# JPC_XE1AP_rev_A.net
KiCad netlist of a schematic drawn in EAGLE
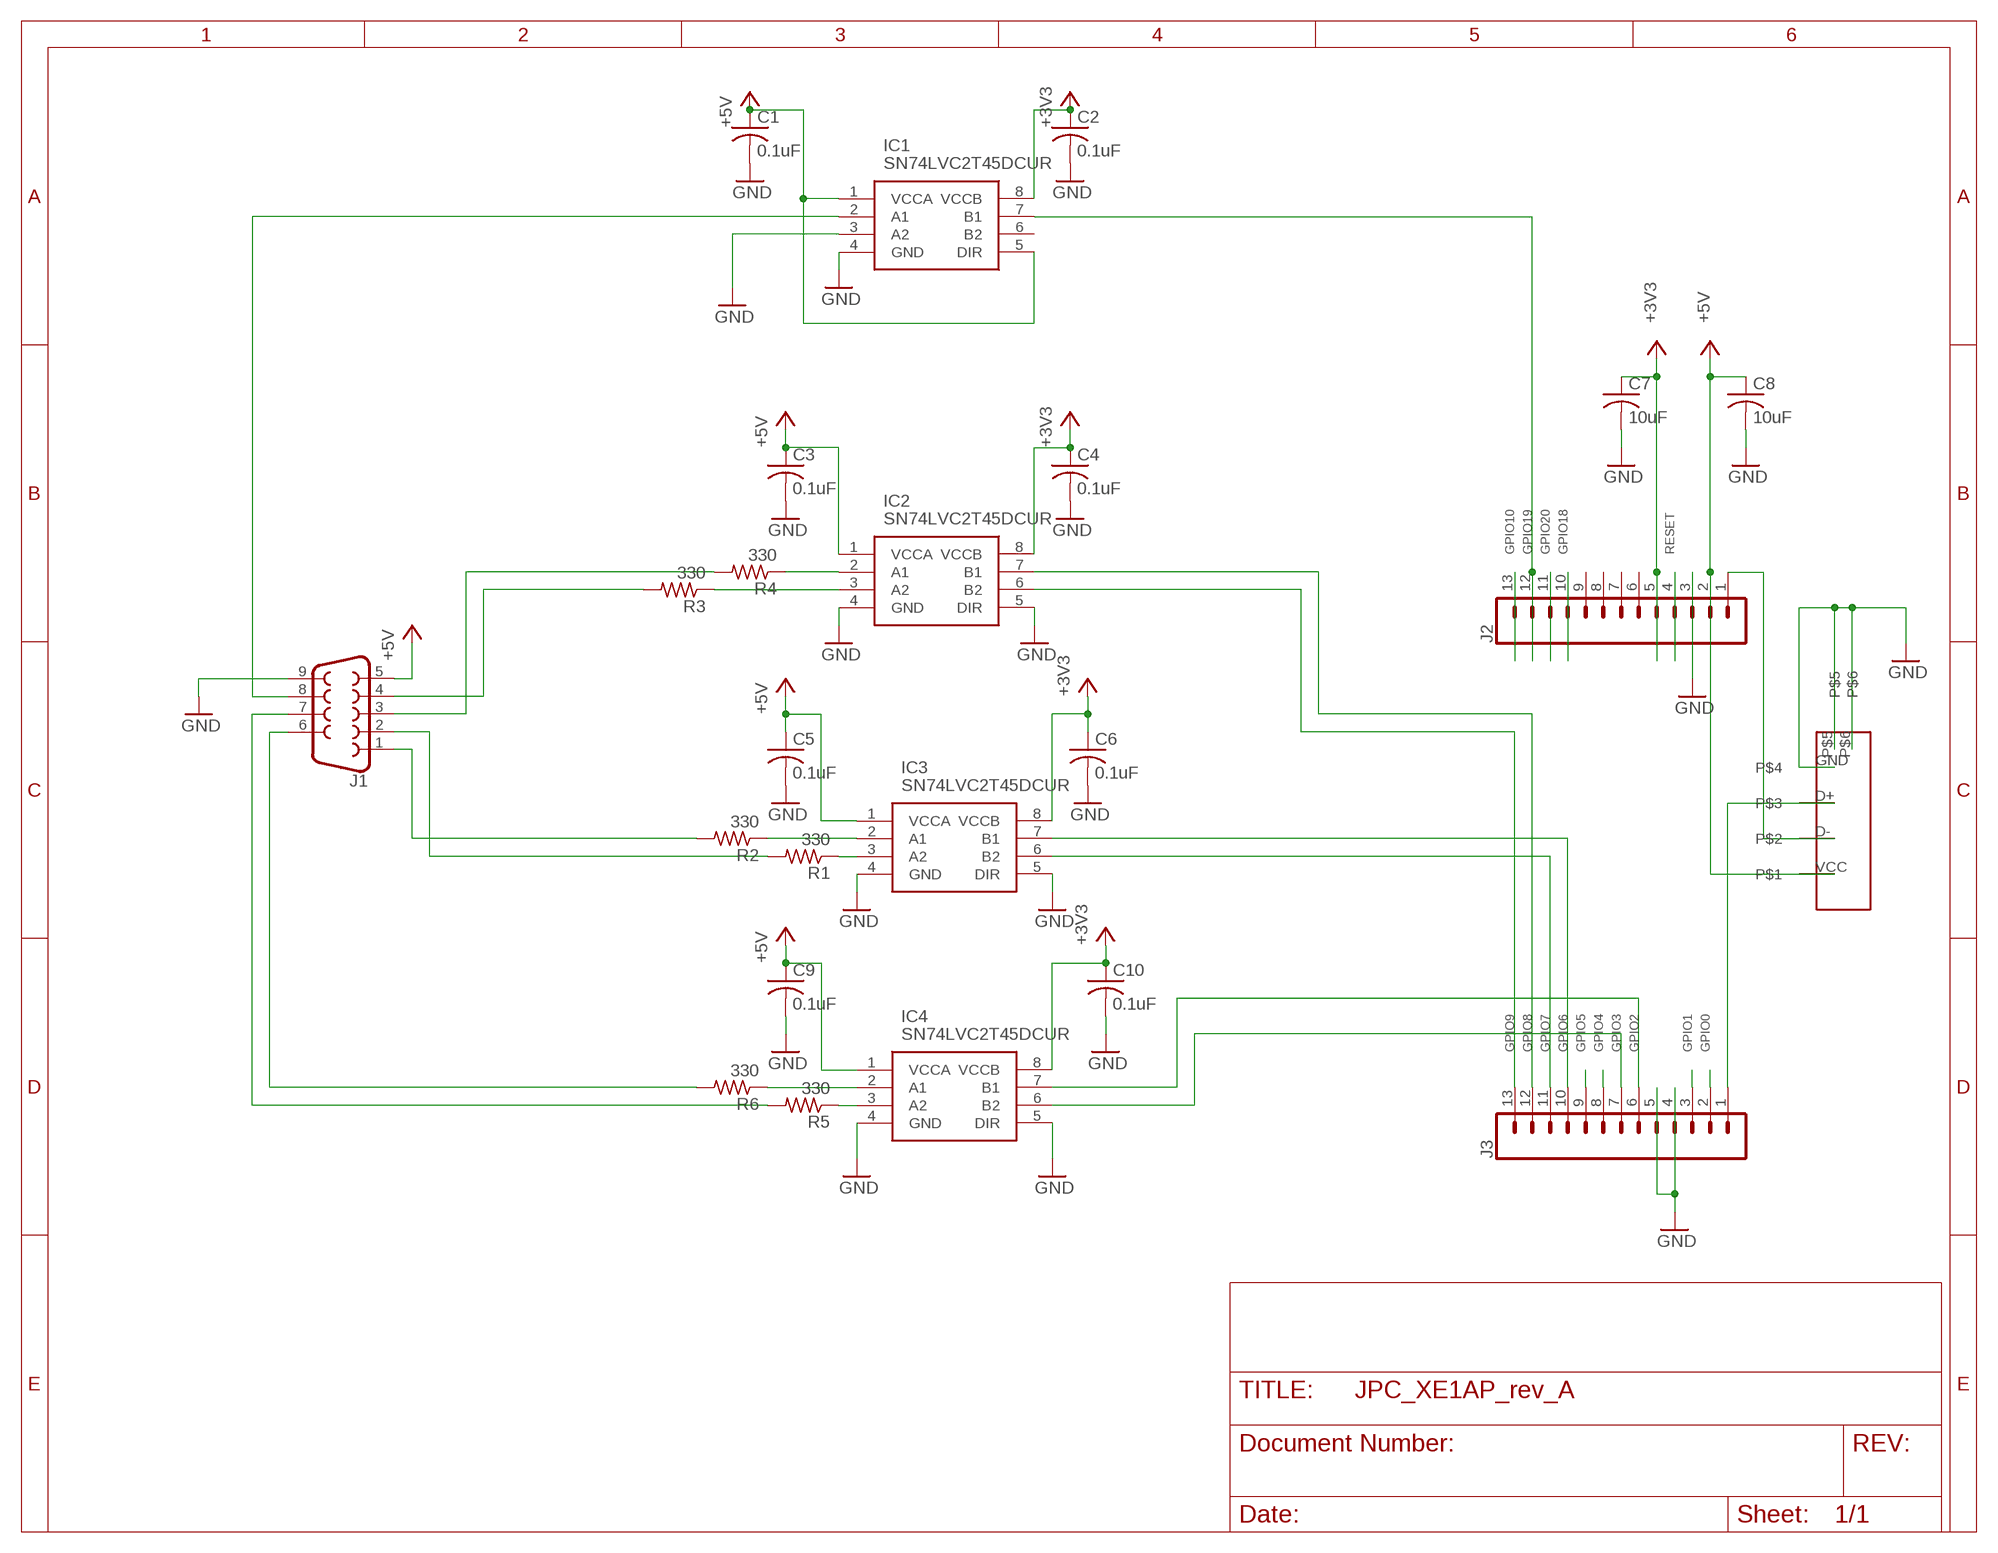
[diagram p0: schematic, sheet 1]

(export (version "E")
  (design (tool "Eeschema 10.0.6"))
  (components
    (comp (ref "C1")
      (value "0.1uF")
      (footprint "eagle-import:C0402")
      (libsource (lib "eagle-import") (part "C-USC0402"))
    )
    (comp (ref "C2")
      (value "0.1uF")
      (footprint "eagle-import:C0402")
      (libsource (lib "eagle-import") (part "C-USC0402"))
    )
    (comp (ref "C3")
      (value "0.1uF")
      (footprint "eagle-import:C0402")
      (libsource (lib "eagle-import") (part "C-USC0402"))
    )
    (comp (ref "C4")
      (value "0.1uF")
      (footprint "eagle-import:C0402")
      (libsource (lib "eagle-import") (part "C-USC0402"))
    )
    (comp (ref "C5")
      (value "0.1uF")
      (footprint "eagle-import:C0402")
      (libsource (lib "eagle-import") (part "C-USC0402"))
    )
    (comp (ref "C6")
      (value "0.1uF")
      (footprint "eagle-import:C0402")
      (libsource (lib "eagle-import") (part "C-USC0402"))
    )
    (comp (ref "C7")
      (value "10uF")
      (footprint "eagle-import:C0805")
      (libsource (lib "eagle-import") (part "resistor_348_C-USC0805"))
    )
    (comp (ref "C8")
      (value "10uF")
      (footprint "eagle-import:C0805")
      (libsource (lib "eagle-import") (part "resistor_348_C-USC0805"))
    )
    (comp (ref "C9")
      (value "0.1uF")
      (footprint "eagle-import:C0402")
      (libsource (lib "eagle-import") (part "C-USC0402"))
    )
    (comp (ref "C10")
      (value "0.1uF")
      (footprint "eagle-import:C0402")
      (libsource (lib "eagle-import") (part "C-USC0402"))
    )
    (comp (ref "IC1")
      (value "SN74LVC2T45DCUR")
      (footprint "eagle-import:SOP50P310X90-8N")
      (fields (field (name "MOUSER_PART_NUMBER") "595-SN74LVC2T45DCUR"))
      (libsource (lib "eagle-import") (part "SN74LVC2T45DCUR"))
    )
    (comp (ref "IC2")
      (value "SN74LVC2T45DCUR")
      (footprint "eagle-import:SOP50P310X90-8N")
      (fields (field (name "MOUSER_PART_NUMBER") "595-SN74LVC2T45DCUR"))
      (libsource (lib "eagle-import") (part "SN74LVC2T45DCUR"))
    )
    (comp (ref "IC3")
      (value "SN74LVC2T45DCUR")
      (footprint "eagle-import:SOP50P310X90-8N")
      (fields (field (name "MOUSER_PART_NUMBER") "595-SN74LVC2T45DCUR"))
      (libsource (lib "eagle-import") (part "SN74LVC2T45DCUR"))
    )
    (comp (ref "IC4")
      (value "SN74LVC2T45DCUR")
      (footprint "eagle-import:SOP50P310X90-8N")
      (fields (field (name "MOUSER_PART_NUMBER") "595-SN74LVC2T45DCUR"))
      (libsource (lib "eagle-import") (part "SN74LVC2T45DCUR"))
    )
    (comp (ref "J1")
      (value "DB9FEMALE")
      (footprint "eagle-import:DB9")
      (libsource (lib "eagle-import") (part "DB9FEMALE"))
    )
    (comp (ref "J2")
      (value "CONN_131X13-LONGPADS-B")
      (footprint "eagle-import:1X13-LONGPADS-B")
      (libsource (lib "eagle-import") (part "CONN_131X13-LONGPADS-B"))
    )
    (comp (ref "J3")
      (value "CONN_13LONGPADS")
      (footprint "eagle-import:1X13-LONGPADS")
      (libsource (lib "eagle-import") (part "CONN_13LONGPADS"))
    )
    (comp (ref "R1")
      (value "330")
      (footprint "eagle-import:R0402")
      (libsource (lib "eagle-import") (part "R-US_R0402"))
    )
    (comp (ref "R2")
      (value "330")
      (footprint "eagle-import:R0402")
      (libsource (lib "eagle-import") (part "R-US_R0402"))
    )
    (comp (ref "R3")
      (value "330")
      (footprint "eagle-import:R0402")
      (libsource (lib "eagle-import") (part "R-US_R0402"))
    )
    (comp (ref "R4")
      (value "330")
      (footprint "eagle-import:R0402")
      (libsource (lib "eagle-import") (part "R-US_R0402"))
    )
    (comp (ref "R5")
      (value "330")
      (footprint "eagle-import:R0402")
      (libsource (lib "eagle-import") (part "R-US_R0402"))
    )
    (comp (ref "R6")
      (value "330")
      (footprint "eagle-import:R0402")
      (libsource (lib "eagle-import") (part "R-US_R0402"))
    )
    (comp (ref "U$1")
      (value "912-121A2026S10100")
      (footprint "eagle-import:912-121A2026S10100")
      (libsource (lib "eagle-import") (part "912-121A2026S10100"))
    )
  )
  (nets
    (net (code "1") (name "+3V3") (class "Default")
      (node (ref "C10") (pin "1") (pinfunction "1_1") (pintype "passive"))
      (node (ref "C2") (pin "1") (pinfunction "1_1") (pintype "passive"))
      (node (ref "C4") (pin "1") (pinfunction "1_1") (pintype "passive"))
      (node (ref "C6") (pin "1") (pinfunction "1_1") (pintype "passive"))
      (node (ref "C7") (pin "1") (pinfunction "1_1") (pintype "passive"))
      (node (ref "IC1") (pin "8") (pinfunction "VCCB_8") (pintype "bidirectional"))
      (node (ref "IC2") (pin "8") (pinfunction "VCCB_8") (pintype "bidirectional"))
      (node (ref "IC3") (pin "8") (pinfunction "VCCB_8") (pintype "bidirectional"))
      (node (ref "IC4") (pin "8") (pinfunction "VCCB_8") (pintype "bidirectional"))
      (node (ref "J2") (pin "5") (pinfunction "5_5") (pintype "passive"))
    )
    (net (code "2") (name "+5V") (class "Default")
      (node (ref "C1") (pin "1") (pinfunction "1_1") (pintype "passive"))
      (node (ref "C3") (pin "1") (pinfunction "1_1") (pintype "passive"))
      (node (ref "C5") (pin "1") (pinfunction "1_1") (pintype "passive"))
      (node (ref "C8") (pin "1") (pinfunction "1_1") (pintype "passive"))
      (node (ref "C9") (pin "1") (pinfunction "1_1") (pintype "passive"))
      (node (ref "IC1") (pin "1") (pinfunction "VCCA_1") (pintype "bidirectional"))
      (node (ref "IC1") (pin "5") (pinfunction "DIR_5") (pintype "bidirectional"))
      (node (ref "IC2") (pin "1") (pinfunction "VCCA_1") (pintype "bidirectional"))
      (node (ref "IC3") (pin "1") (pinfunction "VCCA_1") (pintype "bidirectional"))
      (node (ref "IC4") (pin "1") (pinfunction "VCCA_1") (pintype "bidirectional"))
      (node (ref "J1") (pin "5") (pinfunction "5_5") (pintype "passive"))
      (node (ref "J2") (pin "2") (pinfunction "2_2") (pintype "passive"))
      (node (ref "U$1") (pin "VCC") (pinfunction "P$1_VCC") (pintype "bidirectional"))
    )
    (net (code "3") (name "/GPIO0") (class "Default")
      (node (ref "J3") (pin "2") (pinfunction "2_2") (pintype "passive"))
    )
    (net (code "4") (name "/GPIO1") (class "Default")
      (node (ref "J3") (pin "3") (pinfunction "3_3") (pintype "passive"))
    )
    (net (code "5") (name "/GPIO2") (class "Default")
      (node (ref "IC4") (pin "7") (pinfunction "B1_7") (pintype "bidirectional"))
      (node (ref "J3") (pin "6") (pinfunction "6_6") (pintype "passive"))
    )
    (net (code "6") (name "/GPIO3") (class "Default")
      (node (ref "IC4") (pin "6") (pinfunction "B2_6") (pintype "bidirectional"))
      (node (ref "J3") (pin "7") (pinfunction "7_7") (pintype "passive"))
    )
    (net (code "7") (name "/GPIO4") (class "Default")
      (node (ref "J3") (pin "8") (pinfunction "8_8") (pintype "passive"))
    )
    (net (code "8") (name "/GPIO5") (class "Default")
      (node (ref "J3") (pin "9") (pinfunction "9_9") (pintype "passive"))
    )
    (net (code "9") (name "/GPIO6") (class "Default")
      (node (ref "IC3") (pin "7") (pinfunction "B1_7") (pintype "bidirectional"))
      (node (ref "J3") (pin "10") (pinfunction "10_10") (pintype "passive"))
    )
    (net (code "10") (name "/GPIO7") (class "Default")
      (node (ref "IC3") (pin "6") (pinfunction "B2_6") (pintype "bidirectional"))
      (node (ref "J3") (pin "11") (pinfunction "11_11") (pintype "passive"))
    )
    (net (code "11") (name "/GPIO8") (class "Default")
      (node (ref "IC2") (pin "7") (pinfunction "B1_7") (pintype "bidirectional"))
      (node (ref "J3") (pin "12") (pinfunction "12_12") (pintype "passive"))
    )
    (net (code "12") (name "/GPIO9") (class "Default")
      (node (ref "IC2") (pin "6") (pinfunction "B2_6") (pintype "bidirectional"))
      (node (ref "J3") (pin "13") (pinfunction "13_13") (pintype "passive"))
    )
    (net (code "13") (name "/GPIO10") (class "Default")
      (node (ref "J2") (pin "13") (pinfunction "13_13") (pintype "passive"))
    )
    (net (code "14") (name "/GPIO18") (class "Default")
      (node (ref "J2") (pin "10") (pinfunction "10_10") (pintype "passive"))
    )
    (net (code "15") (name "/GPIO19") (class "Default")
      (node (ref "IC1") (pin "7") (pinfunction "B1_7") (pintype "bidirectional"))
      (node (ref "J2") (pin "12") (pinfunction "12_12") (pintype "passive"))
    )
    (net (code "16") (name "/GPIO20") (class "Default")
      (node (ref "J2") (pin "11") (pinfunction "11_11") (pintype "passive"))
    )
    (net (code "17") (name "/RESET") (class "Default")
      (node (ref "J2") (pin "4") (pinfunction "4_4") (pintype "passive"))
    )
    (net (code "18") (name "GND") (class "Default")
      (node (ref "C1") (pin "2") (pinfunction "2_2") (pintype "passive"))
      (node (ref "C10") (pin "2") (pinfunction "2_2") (pintype "passive"))
      (node (ref "C2") (pin "2") (pinfunction "2_2") (pintype "passive"))
      (node (ref "C3") (pin "2") (pinfunction "2_2") (pintype "passive"))
      (node (ref "C4") (pin "2") (pinfunction "2_2") (pintype "passive"))
      (node (ref "C5") (pin "2") (pinfunction "2_2") (pintype "passive"))
      (node (ref "C6") (pin "2") (pinfunction "2_2") (pintype "passive"))
      (node (ref "C7") (pin "2") (pinfunction "2_2") (pintype "passive"))
      (node (ref "C8") (pin "2") (pinfunction "2_2") (pintype "passive"))
      (node (ref "C9") (pin "2") (pinfunction "2_2") (pintype "passive"))
      (node (ref "IC1") (pin "3") (pinfunction "A2_3") (pintype "bidirectional"))
      (node (ref "IC1") (pin "4") (pinfunction "GND_4") (pintype "bidirectional"))
      (node (ref "IC2") (pin "4") (pinfunction "GND_4") (pintype "bidirectional"))
      (node (ref "IC2") (pin "5") (pinfunction "DIR_5") (pintype "bidirectional"))
      (node (ref "IC3") (pin "4") (pinfunction "GND_4") (pintype "bidirectional"))
      (node (ref "IC3") (pin "5") (pinfunction "DIR_5") (pintype "bidirectional"))
      (node (ref "IC4") (pin "4") (pinfunction "GND_4") (pintype "bidirectional"))
      (node (ref "IC4") (pin "5") (pinfunction "DIR_5") (pintype "bidirectional"))
      (node (ref "J1") (pin "9") (pinfunction "9_9") (pintype "passive"))
      (node (ref "J2") (pin "3") (pinfunction "3_3") (pintype "passive"))
      (node (ref "J3") (pin "4") (pinfunction "4_4") (pintype "passive"))
      (node (ref "J3") (pin "5") (pinfunction "5_5") (pintype "passive"))
      (node (ref "U$1") (pin "GND") (pinfunction "P$4_GND") (pintype "bidirectional"))
      (node (ref "U$1") (pin "P$5") (pinfunction "P$5_P$5") (pintype "bidirectional"))
      (node (ref "U$1") (pin "P$6") (pinfunction "P$6_P$6") (pintype "bidirectional"))
    )
    (net (code "19") (name "Net-(IC1-A1)") (class "Default")
      (node (ref "IC1") (pin "2") (pinfunction "A1_2") (pintype "bidirectional"))
      (node (ref "J1") (pin "8") (pinfunction "8_8") (pintype "passive"))
    )
    (net (code "20") (name "Net-(IC2-A1)") (class "Default")
      (node (ref "IC2") (pin "2") (pinfunction "A1_2") (pintype "bidirectional"))
      (node (ref "R4") (pin "1") (pinfunction "1_1") (pintype "passive"))
    )
    (net (code "21") (name "Net-(IC2-A2)") (class "Default")
      (node (ref "IC2") (pin "3") (pinfunction "A2_3") (pintype "bidirectional"))
      (node (ref "R3") (pin "1") (pinfunction "1_1") (pintype "passive"))
    )
    (net (code "22") (name "Net-(IC3-A1)") (class "Default")
      (node (ref "IC3") (pin "2") (pinfunction "A1_2") (pintype "bidirectional"))
      (node (ref "R2") (pin "1") (pinfunction "1_1") (pintype "passive"))
    )
    (net (code "23") (name "Net-(IC3-A2)") (class "Default")
      (node (ref "IC3") (pin "3") (pinfunction "A2_3") (pintype "bidirectional"))
      (node (ref "R1") (pin "1") (pinfunction "1_1") (pintype "passive"))
    )
    (net (code "24") (name "Net-(IC4-A1)") (class "Default")
      (node (ref "IC4") (pin "2") (pinfunction "A1_2") (pintype "bidirectional"))
      (node (ref "R6") (pin "1") (pinfunction "1_1") (pintype "passive"))
    )
    (net (code "25") (name "Net-(IC4-A2)") (class "Default")
      (node (ref "IC4") (pin "3") (pinfunction "A2_3") (pintype "bidirectional"))
      (node (ref "R5") (pin "1") (pinfunction "1_1") (pintype "passive"))
    )
    (net (code "26") (name "Net-(J1-Pad1)") (class "Default")
      (node (ref "J1") (pin "1") (pinfunction "1_1") (pintype "passive"))
      (node (ref "R2") (pin "2") (pinfunction "2_2") (pintype "passive"))
    )
    (net (code "27") (name "Net-(J1-Pad2)") (class "Default")
      (node (ref "J1") (pin "2") (pinfunction "2_2") (pintype "passive"))
      (node (ref "R1") (pin "2") (pinfunction "2_2") (pintype "passive"))
    )
    (net (code "28") (name "Net-(J1-Pad3)") (class "Default")
      (node (ref "J1") (pin "3") (pinfunction "3_3") (pintype "passive"))
      (node (ref "R4") (pin "2") (pinfunction "2_2") (pintype "passive"))
    )
    (net (code "29") (name "Net-(J1-Pad4)") (class "Default")
      (node (ref "J1") (pin "4") (pinfunction "4_4") (pintype "passive"))
      (node (ref "R3") (pin "2") (pinfunction "2_2") (pintype "passive"))
    )
    (net (code "30") (name "Net-(J1-Pad6)") (class "Default")
      (node (ref "J1") (pin "6") (pinfunction "6_6") (pintype "passive"))
      (node (ref "R6") (pin "2") (pinfunction "2_2") (pintype "passive"))
    )
    (net (code "31") (name "Net-(J1-Pad7)") (class "Default")
      (node (ref "J1") (pin "7") (pinfunction "7_7") (pintype "passive"))
      (node (ref "R5") (pin "2") (pinfunction "2_2") (pintype "passive"))
    )
    (net (code "32") (name "Net-(U$1-P$2)") (class "Default")
      (node (ref "J2") (pin "1") (pinfunction "1_1") (pintype "passive"))
      (node (ref "U$1") (pin "D-") (pinfunction "P$2_D-") (pintype "bidirectional"))
    )
    (net (code "33") (name "Net-(U$1-P$3)") (class "Default")
      (node (ref "J3") (pin "1") (pinfunction "1_1") (pintype "passive"))
      (node (ref "U$1") (pin "D+") (pinfunction "P$3_D+") (pintype "bidirectional"))
    )
    (net (code "34") (name "unconnected-(IC1-B2-Pad6)") (class "Default")
      (node (ref "IC1") (pin "6") (pinfunction "B2_6") (pintype "bidirectional"))
    )
    (net (code "35") (name "unconnected-(J2-Pad6)") (class "Default")
      (node (ref "J2") (pin "6") (pinfunction "6_6") (pintype "passive"))
    )
    (net (code "36") (name "unconnected-(J2-Pad7)") (class "Default")
      (node (ref "J2") (pin "7") (pinfunction "7_7") (pintype "passive"))
    )
    (net (code "37") (name "unconnected-(J2-Pad8)") (class "Default")
      (node (ref "J2") (pin "8") (pinfunction "8_8") (pintype "passive"))
    )
    (net (code "38") (name "unconnected-(J2-Pad9)") (class "Default")
      (node (ref "J2") (pin "9") (pinfunction "9_9") (pintype "passive"))
    )
  )
)
